# ESC_Schematic_0.net
KiCad netlist of a schematic drawn in Altium Designer
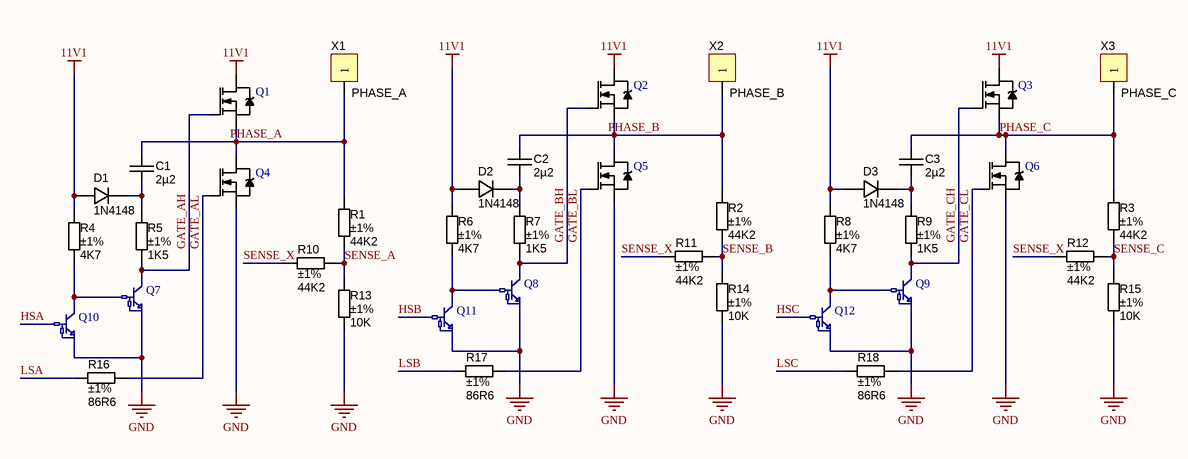
[diagram p0: ESC_Schematic_0.SchDoc]

(export (version "E")
  (design (tool "Eeschema 10.0.6"))
  (components
    (comp (ref "C1")
      (value "2µ2")
      (footprint "CAPC2012X135N")
      (description "Capacitor SMD Cer 2.2uF 10% 16V X7R 0805")
      (fields (field (name "TOLERANCE") "±10%") (field (name "Comment") "approved sub OK"))
      (libsource (lib "PBL - Capacitors") (part "CAPC_2u2_0805"))
    )
    (comp (ref "C2")
      (value "2µ2")
      (footprint "CAPC2012X135N")
      (description "Capacitor SMD Cer 2.2uF 10% 16V X7R 0805")
      (fields (field (name "TOLERANCE") "±10%") (field (name "Comment") "approved sub OK"))
      (libsource (lib "PBL - Capacitors") (part "CAPC_2u2_0805"))
    )
    (comp (ref "C3")
      (value "2µ2")
      (footprint "CAPC2012X135N")
      (description "Capacitor SMD Cer 2.2uF 10% 16V X7R 0805")
      (fields (field (name "TOLERANCE") "±10%") (field (name "Comment") "approved sub OK"))
      (libsource (lib "PBL - Capacitors") (part "CAPC_2u2_0805"))
    )
    (comp (ref "D1")
      (value "1N4148")
      (footprint "SOD523F")
      (description "Diode SMD small signal 0.2A SOD-523F")
      (libsource (lib "PBL - Diodes") (part "DIODE_1N4148_200mA_SOD523F"))
    )
    (comp (ref "D2")
      (value "1N4148")
      (footprint "SOD523F")
      (description "Diode SMD small signal 0.2A SOD-523F")
      (libsource (lib "PBL - Diodes") (part "DIODE_1N4148_200mA_SOD523F"))
    )
    (comp (ref "D3")
      (value "1N4148")
      (footprint "SOD523F")
      (description "Diode SMD small signal 0.2A SOD-523F")
      (libsource (lib "PBL - Diodes") (part "DIODE_1N4148_200mA_SOD523F"))
    )
    (comp (ref "Q1")
      (value "*")
      (footprint "TO-252_1")
      (description "PHD82N N-Channel MOSFET transistor")
      (libsource (lib "co2_meter_integrated_library") (part "PHD82N"))
    )
    (comp (ref "Q2")
      (value "*")
      (footprint "TO-252_1")
      (description "PHD82N N-Channel MOSFET transistor")
      (libsource (lib "co2_meter_integrated_library") (part "PHD82N"))
    )
    (comp (ref "Q3")
      (value "*")
      (footprint "TO-252_1")
      (description "PHD82N N-Channel MOSFET transistor")
      (libsource (lib "co2_meter_integrated_library") (part "PHD82N"))
    )
    (comp (ref "Q4")
      (value "*")
      (footprint "TO-252_1")
      (description "PHD82N N-Channel MOSFET transistor")
      (libsource (lib "co2_meter_integrated_library") (part "PHD82N"))
    )
    (comp (ref "Q5")
      (value "*")
      (footprint "TO-252_1")
      (description "PHD82N N-Channel MOSFET transistor")
      (libsource (lib "co2_meter_integrated_library") (part "PHD82N"))
    )
    (comp (ref "Q6")
      (value "*")
      (footprint "TO-252_1")
      (description "PHD82N N-Channel MOSFET transistor")
      (libsource (lib "co2_meter_integrated_library") (part "PHD82N"))
    )
    (comp (ref "Q7")
      (value "*")
      (footprint "TO-236")
      (description "NPN Resistor-Equipped Transistor (RET)")
      (libsource (lib "co2_meter_integrated_library") (part "PDTC143Z"))
    )
    (comp (ref "Q8")
      (value "*")
      (footprint "TO-236")
      (description "NPN Resistor-Equipped Transistor (RET)")
      (libsource (lib "co2_meter_integrated_library") (part "PDTC143Z"))
    )
    (comp (ref "Q9")
      (value "*")
      (footprint "TO-236")
      (description "NPN Resistor-Equipped Transistor (RET)")
      (libsource (lib "co2_meter_integrated_library") (part "PDTC143Z"))
    )
    (comp (ref "Q10")
      (value "*")
      (footprint "TO-236")
      (description "NPN Resistor-Equipped Transistor (RET)")
      (libsource (lib "co2_meter_integrated_library") (part "PDTC143Z"))
    )
    (comp (ref "Q11")
      (value "*")
      (footprint "TO-236")
      (description "NPN Resistor-Equipped Transistor (RET)")
      (libsource (lib "co2_meter_integrated_library") (part "PDTC143Z"))
    )
    (comp (ref "Q12")
      (value "*")
      (footprint "TO-236")
      (description "NPN Resistor-Equipped Transistor (RET)")
      (libsource (lib "co2_meter_integrated_library") (part "PDTC143Z"))
    )
    (comp (ref "R1")
      (value "44K2")
      (footprint "RESC2012X70N")
      (description "Resistor SMD chip 44.2k Ohm 0.125W 1% 0805")
      (fields (field (name "TOLERANCE") "±1%") (field (name "Comment") "Thick Film"))
      (libsource (lib "PBL - Resistors") (part "RES_44K2_0805_1%"))
    )
    (comp (ref "R2")
      (value "44K2")
      (footprint "RESC2012X70N")
      (description "Resistor SMD chip 44.2k Ohm 0.125W 1% 0805")
      (fields (field (name "TOLERANCE") "±1%") (field (name "Comment") "Thick Film"))
      (libsource (lib "PBL - Resistors") (part "RES_44K2_0805_1%"))
    )
    (comp (ref "R3")
      (value "44K2")
      (footprint "RESC2012X70N")
      (description "Resistor SMD chip 44.2k Ohm 0.125W 1% 0805")
      (fields (field (name "TOLERANCE") "±1%") (field (name "Comment") "Thick Film"))
      (libsource (lib "PBL - Resistors") (part "RES_44K2_0805_1%"))
    )
    (comp (ref "R4")
      (value "4K7")
      (footprint "RESC2012X70N")
      (description "Resistor SMD chip 4.7k Ohm 0.125W 1% 0805")
      (fields (field (name "TOLERANCE") "±1%") (field (name "Comment") "Thick Film"))
      (libsource (lib "PBL - Resistors") (part "RES_4K7_0805_1%"))
    )
    (comp (ref "R5")
      (value "1K5")
      (footprint "RESC2012X70N")
      (description "Resistor SMD chip 1.5k Ohm 0.125W 1% 0805")
      (fields (field (name "TOLERANCE") "±1%") (field (name "Comment") "Thick Film"))
      (libsource (lib "PBL - Resistors") (part "RES_1K5_0805_1%"))
    )
    (comp (ref "R6")
      (value "4K7")
      (footprint "RESC2012X70N")
      (description "Resistor SMD chip 4.7k Ohm 0.125W 1% 0805")
      (fields (field (name "TOLERANCE") "±1%") (field (name "Comment") "Thick Film"))
      (libsource (lib "PBL - Resistors") (part "RES_4K7_0805_1%"))
    )
    (comp (ref "R7")
      (value "1K5")
      (footprint "RESC2012X70N")
      (description "Resistor SMD chip 1.5k Ohm 0.125W 1% 0805")
      (fields (field (name "TOLERANCE") "±1%") (field (name "Comment") "Thick Film"))
      (libsource (lib "PBL - Resistors") (part "RES_1K5_0805_1%"))
    )
    (comp (ref "R8")
      (value "4K7")
      (footprint "RESC2012X70N")
      (description "Resistor SMD chip 4.7k Ohm 0.125W 1% 0805")
      (fields (field (name "TOLERANCE") "±1%") (field (name "Comment") "Thick Film"))
      (libsource (lib "PBL - Resistors") (part "RES_4K7_0805_1%"))
    )
    (comp (ref "R9")
      (value "1K5")
      (footprint "RESC2012X70N")
      (description "Resistor SMD chip 1.5k Ohm 0.125W 1% 0805")
      (fields (field (name "TOLERANCE") "±1%") (field (name "Comment") "Thick Film"))
      (libsource (lib "PBL - Resistors") (part "RES_1K5_0805_1%"))
    )
    (comp (ref "R10")
      (value "44K2")
      (footprint "RESC2012X70N")
      (description "Resistor SMD chip 44.2k Ohm 0.125W 1% 0805")
      (fields (field (name "TOLERANCE") "±1%") (field (name "Comment") "Thick Film"))
      (libsource (lib "") (part "RES_44K2_0805_1%_1"))
    )
    (comp (ref "R11")
      (value "44K2")
      (footprint "RESC2012X70N")
      (description "Resistor SMD chip 44.2k Ohm 0.125W 1% 0805")
      (fields (field (name "TOLERANCE") "±1%") (field (name "Comment") "Thick Film"))
      (libsource (lib "") (part "RES_44K2_0805_1%_1"))
    )
    (comp (ref "R12")
      (value "44K2")
      (footprint "RESC2012X70N")
      (description "Resistor SMD chip 44.2k Ohm 0.125W 1% 0805")
      (fields (field (name "TOLERANCE") "±1%") (field (name "Comment") "Thick Film"))
      (libsource (lib "") (part "RES_44K2_0805_1%_1"))
    )
    (comp (ref "R13")
      (value "10K")
      (footprint "RESC2012X70N")
      (description "Resistor SMD chip 10k Ohm 0.125W 1% 0805")
      (fields (field (name "TOLERANCE") "±1%") (field (name "Comment") "Thick Film"))
      (libsource (lib "PBL - Resistors") (part "RES_10K_0805_1%"))
    )
    (comp (ref "R14")
      (value "10K")
      (footprint "RESC2012X70N")
      (description "Resistor SMD chip 10k Ohm 0.125W 1% 0805")
      (fields (field (name "TOLERANCE") "±1%") (field (name "Comment") "Thick Film"))
      (libsource (lib "PBL - Resistors") (part "RES_10K_0805_1%"))
    )
    (comp (ref "R15")
      (value "10K")
      (footprint "RESC2012X70N")
      (description "Resistor SMD chip 10k Ohm 0.125W 1% 0805")
      (fields (field (name "TOLERANCE") "±1%") (field (name "Comment") "Thick Film"))
      (libsource (lib "PBL - Resistors") (part "RES_10K_0805_1%"))
    )
    (comp (ref "R16")
      (value "86R6")
      (footprint "RESC2012X70N")
      (description "Resistor SMD chip 86.6 Ohm 0.125W 1% 0805")
      (fields
        (field (name "MANUFACTURER") "Vishay/Dale")
        (field (name "MANUFACTURER PART NUMBER") "CRCW080586R6FKEA")
        (field (name "TOLERANCE") "±1%")
      )
      (libsource (lib "PBL - Resistors") (part "RES_86R6_0805_1%"))
    )
    (comp (ref "R17")
      (value "86R6")
      (footprint "RESC2012X70N")
      (description "Resistor SMD chip 86.6 Ohm 0.125W 1% 0805")
      (fields
        (field (name "MANUFACTURER") "Vishay/Dale")
        (field (name "MANUFACTURER PART NUMBER") "CRCW080586R6FKEA")
        (field (name "TOLERANCE") "±1%")
      )
      (libsource (lib "PBL - Resistors") (part "RES_86R6_0805_1%"))
    )
    (comp (ref "R18")
      (value "86R6")
      (footprint "RESC2012X70N")
      (description "Resistor SMD chip 86.6 Ohm 0.125W 1% 0805")
      (fields
        (field (name "MANUFACTURER") "Vishay/Dale")
        (field (name "MANUFACTURER PART NUMBER") "CRCW080586R6FKEA")
        (field (name "TOLERANCE") "±1%")
      )
      (libsource (lib "PBL - Resistors") (part "RES_86R6_0805_1%"))
    )
    (comp (ref "X1")
      (value "PHASE_A")
      (footprint "THP_D38_T75_B125")
      (libsource (lib "PBL - Pads and Jumpers") (part "Term1"))
    )
    (comp (ref "X2")
      (value "PHASE_B")
      (footprint "THP_D38_T75_B125")
      (libsource (lib "PBL - Pads and Jumpers") (part "Term1"))
    )
    (comp (ref "X3")
      (value "PHASE_C")
      (footprint "THP_D38_T75_B125")
      (libsource (lib "PBL - Pads and Jumpers") (part "Term1"))
    )
  )
  (nets
    (net (code "1") (name "/GATE_AH") (class "Default")
      (node (ref "Q1") (pin "1") (pinfunction "G_1") (pintype "passive"))
      (node (ref "Q7") (pin "3") (pinfunction "C_3") (pintype "power_in"))
      (node (ref "R5") (pin "2") (pinfunction "2_2") (pintype "passive"))
    )
    (net (code "2") (name "/GATE_AL") (class "Default")
      (node (ref "Q4") (pin "1") (pinfunction "G_1") (pintype "passive"))
      (node (ref "R16") (pin "2") (pinfunction "2_2") (pintype "passive"))
    )
    (net (code "3") (name "/GATE_BH") (class "Default")
      (node (ref "Q2") (pin "1") (pinfunction "G_1") (pintype "passive"))
      (node (ref "Q8") (pin "3") (pinfunction "C_3") (pintype "power_in"))
      (node (ref "R7") (pin "2") (pinfunction "2_2") (pintype "passive"))
    )
    (net (code "4") (name "/GATE_BL") (class "Default")
      (node (ref "Q5") (pin "1") (pinfunction "G_1") (pintype "passive"))
      (node (ref "R17") (pin "2") (pinfunction "2_2") (pintype "passive"))
    )
    (net (code "5") (name "/GATE_CH") (class "Default")
      (node (ref "Q3") (pin "1") (pinfunction "G_1") (pintype "passive"))
      (node (ref "Q9") (pin "3") (pinfunction "C_3") (pintype "power_in"))
      (node (ref "R9") (pin "2") (pinfunction "2_2") (pintype "passive"))
    )
    (net (code "6") (name "/GATE_CL") (class "Default")
      (node (ref "Q6") (pin "1") (pinfunction "G_1") (pintype "passive"))
      (node (ref "R18") (pin "2") (pinfunction "2_2") (pintype "passive"))
    )
    (net (code "7") (name "/HSA") (class "Default")
      (node (ref "Q10") (pin "1") (pinfunction "B_1") (pintype "power_in"))
    )
    (net (code "8") (name "/HSB") (class "Default")
      (node (ref "Q11") (pin "1") (pinfunction "B_1") (pintype "power_in"))
    )
    (net (code "9") (name "/HSC") (class "Default")
      (node (ref "Q12") (pin "1") (pinfunction "B_1") (pintype "power_in"))
    )
    (net (code "10") (name "/LSA") (class "Default")
      (node (ref "R16") (pin "1") (pinfunction "1_1") (pintype "passive"))
    )
    (net (code "11") (name "/LSB") (class "Default")
      (node (ref "R17") (pin "1") (pinfunction "1_1") (pintype "passive"))
    )
    (net (code "12") (name "/LSC") (class "Default")
      (node (ref "R18") (pin "1") (pinfunction "1_1") (pintype "passive"))
    )
    (net (code "13") (name "/PHASE_A") (class "Default")
      (node (ref "C1") (pin "1") (pintype "passive"))
      (node (ref "Q1") (pin "2") (pinfunction "S_2") (pintype "passive"))
      (node (ref "Q4") (pin "3") (pinfunction "D_3") (pintype "passive"))
      (node (ref "R1") (pin "1") (pinfunction "1_1") (pintype "passive"))
      (node (ref "X1") (pin "1") (pinfunction "1_1") (pintype "passive"))
    )
    (net (code "14") (name "/PHASE_B") (class "Default")
      (node (ref "C2") (pin "1") (pintype "passive"))
      (node (ref "Q2") (pin "2") (pinfunction "S_2") (pintype "passive"))
      (node (ref "Q5") (pin "3") (pinfunction "D_3") (pintype "passive"))
      (node (ref "R2") (pin "1") (pinfunction "1_1") (pintype "passive"))
      (node (ref "X2") (pin "1") (pinfunction "1_1") (pintype "passive"))
    )
    (net (code "15") (name "/PHASE_C") (class "Default")
      (node (ref "C3") (pin "1") (pintype "passive"))
      (node (ref "Q3") (pin "2") (pinfunction "S_2") (pintype "passive"))
      (node (ref "Q6") (pin "3") (pinfunction "D_3") (pintype "passive"))
      (node (ref "R3") (pin "1") (pinfunction "1_1") (pintype "passive"))
      (node (ref "X3") (pin "1") (pinfunction "1_1") (pintype "passive"))
    )
    (net (code "16") (name "/SENSE_A") (class "Default")
      (node (ref "R1") (pin "2") (pinfunction "2_2") (pintype "passive"))
      (node (ref "R10") (pin "2") (pinfunction "2_2") (pintype "passive"))
      (node (ref "R13") (pin "1") (pinfunction "1_1") (pintype "passive"))
    )
    (net (code "17") (name "/SENSE_B") (class "Default")
      (node (ref "R11") (pin "2") (pinfunction "2_2") (pintype "passive"))
      (node (ref "R14") (pin "1") (pinfunction "1_1") (pintype "passive"))
      (node (ref "R2") (pin "2") (pinfunction "2_2") (pintype "passive"))
    )
    (net (code "18") (name "/SENSE_C") (class "Default")
      (node (ref "R12") (pin "2") (pinfunction "2_2") (pintype "passive"))
      (node (ref "R15") (pin "1") (pinfunction "1_1") (pintype "passive"))
      (node (ref "R3") (pin "2") (pinfunction "2_2") (pintype "passive"))
    )
    (net (code "19") (name "/SENSE_X") (class "Default")
      (node (ref "R10") (pin "1") (pinfunction "1_1") (pintype "passive"))
      (node (ref "R11") (pin "1") (pinfunction "1_1") (pintype "passive"))
      (node (ref "R12") (pin "1") (pinfunction "1_1") (pintype "passive"))
    )
    (net (code "20") (name "11V1") (class "Default")
      (node (ref "D1") (pin "A") (pinfunction "A_A") (pintype "passive"))
      (node (ref "D2") (pin "A") (pinfunction "A_A") (pintype "passive"))
      (node (ref "D3") (pin "A") (pinfunction "A_A") (pintype "passive"))
      (node (ref "Q1") (pin "3") (pinfunction "D_3") (pintype "passive"))
      (node (ref "Q2") (pin "3") (pinfunction "D_3") (pintype "passive"))
      (node (ref "Q3") (pin "3") (pinfunction "D_3") (pintype "passive"))
      (node (ref "R4") (pin "1") (pinfunction "1_1") (pintype "passive"))
      (node (ref "R6") (pin "1") (pinfunction "1_1") (pintype "passive"))
      (node (ref "R8") (pin "1") (pinfunction "1_1") (pintype "passive"))
    )
    (net (code "21") (name "GND") (class "Default")
      (node (ref "Q10") (pin "2") (pinfunction "E_2") (pintype "power_in"))
      (node (ref "Q11") (pin "2") (pinfunction "E_2") (pintype "power_in"))
      (node (ref "Q12") (pin "2") (pinfunction "E_2") (pintype "power_in"))
      (node (ref "Q4") (pin "2") (pinfunction "S_2") (pintype "passive"))
      (node (ref "Q5") (pin "2") (pinfunction "S_2") (pintype "passive"))
      (node (ref "Q6") (pin "2") (pinfunction "S_2") (pintype "passive"))
      (node (ref "Q7") (pin "2") (pinfunction "E_2") (pintype "power_in"))
      (node (ref "Q8") (pin "2") (pinfunction "E_2") (pintype "power_in"))
      (node (ref "Q9") (pin "2") (pinfunction "E_2") (pintype "power_in"))
      (node (ref "R13") (pin "2") (pinfunction "2_2") (pintype "passive"))
      (node (ref "R14") (pin "2") (pinfunction "2_2") (pintype "passive"))
      (node (ref "R15") (pin "2") (pinfunction "2_2") (pintype "passive"))
    )
    (net (code "22") (name "Net-(C1-Pad2)") (class "Default")
      (node (ref "C1") (pin "2") (pintype "passive"))
      (node (ref "D1") (pin "K") (pinfunction "K_K") (pintype "passive"))
      (node (ref "R5") (pin "1") (pinfunction "1_1") (pintype "passive"))
    )
    (net (code "23") (name "Net-(C2-Pad2)") (class "Default")
      (node (ref "C2") (pin "2") (pintype "passive"))
      (node (ref "D2") (pin "K") (pinfunction "K_K") (pintype "passive"))
      (node (ref "R7") (pin "1") (pinfunction "1_1") (pintype "passive"))
    )
    (net (code "24") (name "Net-(C3-Pad2)") (class "Default")
      (node (ref "C3") (pin "2") (pintype "passive"))
      (node (ref "D3") (pin "K") (pinfunction "K_K") (pintype "passive"))
      (node (ref "R9") (pin "1") (pinfunction "1_1") (pintype "passive"))
    )
    (net (code "25") (name "Net-(Q10-C)") (class "Default")
      (node (ref "Q10") (pin "3") (pinfunction "C_3") (pintype "power_in"))
      (node (ref "Q7") (pin "1") (pinfunction "B_1") (pintype "power_in"))
      (node (ref "R4") (pin "2") (pinfunction "2_2") (pintype "passive"))
    )
    (net (code "26") (name "Net-(Q11-C)") (class "Default")
      (node (ref "Q11") (pin "3") (pinfunction "C_3") (pintype "power_in"))
      (node (ref "Q8") (pin "1") (pinfunction "B_1") (pintype "power_in"))
      (node (ref "R6") (pin "2") (pinfunction "2_2") (pintype "passive"))
    )
    (net (code "27") (name "Net-(Q12-C)") (class "Default")
      (node (ref "Q12") (pin "3") (pinfunction "C_3") (pintype "power_in"))
      (node (ref "Q9") (pin "1") (pinfunction "B_1") (pintype "power_in"))
      (node (ref "R8") (pin "2") (pinfunction "2_2") (pintype "passive"))
    )
  )
)
